# SENSOR.net
KiCad netlist of a schematic drawn in Altium Designer
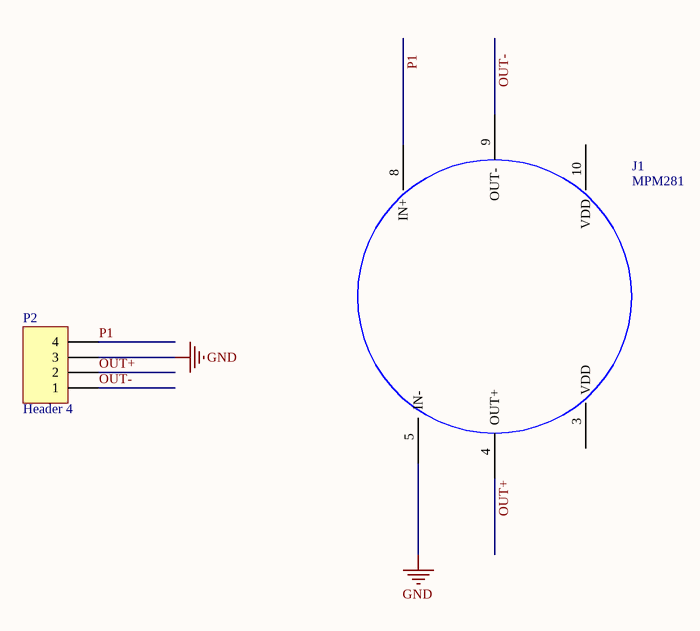
[diagram p0: SENSOR.SchDoc]

(export (version "E")
  (design (tool "Eeschema 10.0.6"))
  (components
    (comp (ref "J1")
      (value "MPM281")
      (footprint "MPM281")
      (libsource (lib "Schlib_20110825") (part "MPM281"))
    )
    (comp (ref "P2")
      (value "Header 4")
      (footprint "HDR1X4")
      (description "Header, 4-Pin")
      (fields (field (name "PUBLISHER") "Altium Limited"))
      (libsource (lib "Miscellaneous Connectors") (part "Header 4"))
    )
  )
  (nets
    (net (code "1") (name "/OUT+") (class "Default")
      (node (ref "J1") (pin "4") (pinfunction "OUT+_4") (pintype "passive"))
      (node (ref "P2") (pin "2") (pinfunction "2_2") (pintype "passive"))
    )
    (net (code "2") (name "/OUT-") (class "Default")
      (node (ref "J1") (pin "9") (pinfunction "OUT-_9") (pintype "passive"))
      (node (ref "P2") (pin "1") (pinfunction "1_1") (pintype "passive"))
    )
    (net (code "3") (name "/P1") (class "Default")
      (node (ref "J1") (pin "8") (pinfunction "IN+_8") (pintype "passive"))
      (node (ref "P2") (pin "4") (pinfunction "4_4") (pintype "passive"))
    )
    (net (code "4") (name "GND") (class "Default")
      (node (ref "J1") (pin "5") (pinfunction "IN-_5") (pintype "passive"))
      (node (ref "P2") (pin "3") (pinfunction "3_3") (pintype "passive"))
    )
    (net (code "5") (name "unconnected-(J1-VDD-Pad3)") (class "Default")
      (node (ref "J1") (pin "3") (pinfunction "VDD_3") (pintype "passive"))
    )
    (net (code "6") (name "unconnected-(J1-VDD-Pad10)") (class "Default")
      (node (ref "J1") (pin "10") (pinfunction "VDD_10") (pintype "passive"))
    )
  )
)
